# MCU.net
KiCad netlist of a schematic drawn in Altium Designer
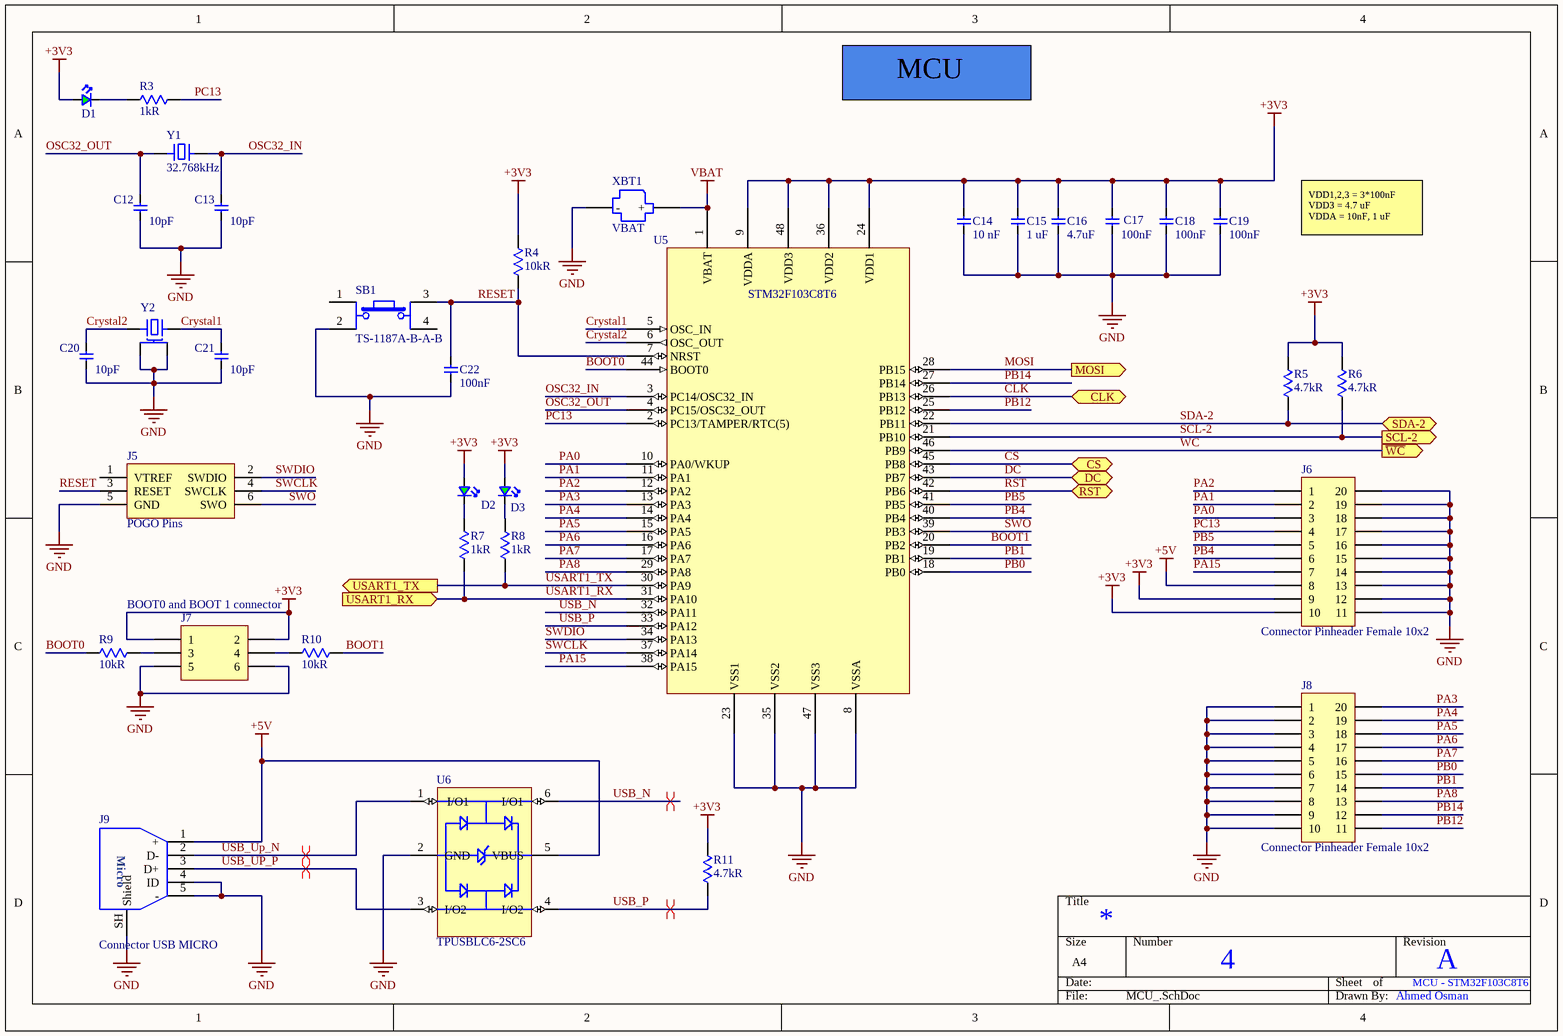
[diagram p0: MCU_.SchDoc]

(export (version "E")
  (design (tool "Eeschema 10.0.6"))
  (components
    (comp (ref "C12")
      (value "10pF")
      (footprint "CAP 0603")
      (description "10 pF ±5% 50V Ceramic Capacitor C0G, NP0 0603 (1608 Metric)")
      (fields (field (name "TOLERANCE") "5%") (field (name "VOLTAGE") "50V"))
      (libsource (lib "Temperature project symbols") (part "CAP  0603 10 pF ±5% 50V"))
    )
    (comp (ref "C13")
      (value "10pF")
      (footprint "CAP 0603")
      (description "10 pF ±5% 50V Ceramic Capacitor C0G, NP0 0603 (1608 Metric)")
      (fields (field (name "TOLERANCE") "5%") (field (name "VOLTAGE") "50V"))
      (libsource (lib "Temperature project symbols") (part "CAP  0603 10 pF ±5% 50V"))
    )
    (comp (ref "C14")
      (value "10 nF")
      (footprint "CAP 0603")
      (description "10000 pF ±10% 25V Ceramic Capacitor X7R 0603 (1608 Metric)")
      (libsource (lib "Temperature project symbols") (part "CAP  0603 10 nF ±10% 25V"))
    )
    (comp (ref "C15")
      (value "1 uF")
      (footprint "CAP 0603")
      (description "1 µF ±10% 25V Ceramic Capacitor X5R 0603 (1608 Metric)")
      (fields (field (name "MANUFACTURER") "Yageo") (field (name "TOLERANCE") "10%"))
      (libsource (lib "Temperature project symbols") (part "CAP  0603 1 µF ±10% 25V"))
    )
    (comp (ref "C16")
      (value "4.7uF")
      (footprint "CAP 0603")
      (description "4.7 µF ±10% 35V Ceramic Capacitor X5R 0603 (1608 Metric)")
      (fields (field (name "TOLERANCE") "10%") (field (name "VOLTAGE") "35V"))
      (libsource (lib "Temperature project symbols") (part "CAP  0603 4.7 µF ±10% 35V"))
    )
    (comp (ref "C17")
      (value "100nF")
      (footprint "CAP 0603")
      (description "0.1 µF ±10% 50V Ceramic Capacitor X7R 0603 (1608 Metric)")
      (fields (field (name "TOLERANCE") "10%") (field (name "VOLTAGE") "50V"))
      (libsource (lib "Temperature project symbols") (part "CAP  0603 100nF 10% 50 V"))
    )
    (comp (ref "C18")
      (value "100nF")
      (footprint "CAP 0603")
      (description "0.1 µF ±10% 50V Ceramic Capacitor X7R 0603 (1608 Metric)")
      (fields (field (name "TOLERANCE") "10%") (field (name "VOLTAGE") "50V"))
      (libsource (lib "Temperature project symbols") (part "CAP  0603 100nF 10% 50 V"))
    )
    (comp (ref "C19")
      (value "100nF")
      (footprint "CAP 0603")
      (description "0.1 µF ±10% 50V Ceramic Capacitor X7R 0603 (1608 Metric)")
      (fields (field (name "TOLERANCE") "10%") (field (name "VOLTAGE") "50V"))
      (libsource (lib "") (part "CAP  0603 100nF 10% 50 V_1"))
    )
    (comp (ref "C20")
      (value "10pF")
      (footprint "CAP 0603")
      (description "10 pF ±5% 50V Ceramic Capacitor C0G, NP0 0603 (1608 Metric)")
      (fields (field (name "TOLERANCE") "5%") (field (name "VOLTAGE") "50V"))
      (libsource (lib "Temperature project symbols") (part "CAP  0603 10 pF ±5% 50V"))
    )
    (comp (ref "C21")
      (value "10pF")
      (footprint "CAP 0603")
      (description "10 pF ±5% 50V Ceramic Capacitor C0G, NP0 0603 (1608 Metric)")
      (fields (field (name "TOLERANCE") "5%") (field (name "VOLTAGE") "50V"))
      (libsource (lib "Temperature project symbols") (part "CAP  0603 10 pF ±5% 50V"))
    )
    (comp (ref "C22")
      (value "100nF")
      (footprint "CAP 0603")
      (description "0.1 µF ±10% 50V Ceramic Capacitor X7R 0603 (1608 Metric)")
      (fields (field (name "TOLERANCE") "10%") (field (name "VOLTAGE") "50V"))
      (libsource (lib "Temperature project symbols") (part "CAP  0603 100 nF 10% 50 V"))
    )
    (comp (ref "D1")
      (value "LED GREEN")
      (footprint "LED GREEN")
      (description "Green 520nm LED Indication - Discrete 3.2V 0603 (1608 Metric)")
      (libsource (lib "Temperature project symbols") (part "LED GREEN"))
    )
    (comp (ref "D2")
      (value "LED GREEN")
      (footprint "LED GREEN")
      (description "Green 520nm LED Indication - Discrete 3.2V 0603 (1608 Metric)")
      (libsource (lib "Temperature project symbols") (part "LED GREEN"))
    )
    (comp (ref "D3")
      (value "LED GREEN")
      (footprint "LED GREEN")
      (description "Green 520nm LED Indication - Discrete 3.2V 0603 (1608 Metric)")
      (libsource (lib "Temperature project symbols") (part "LED GREEN"))
    )
    (comp (ref "J5")
      (value "POGO Pins")
      (footprint "SEGGER_8.06.16_J-LINK_6-PIN_NEEDLE_ADAPTER")
      (description "Plug-Of-Nails™ Cable Assembly")
      (libsource (lib "Temperature project symbols") (part "POGO Pins"))
    )
    (comp (ref "J6")
      (value "Connector Pinheader Female 10x2")
      (footprint "Connector Pinheader 10x2")
      (description "20 Position Header Connector 0.100\" (2.54mm) Through Hole Gold")
      (fields (field (name "MANUFACTURER") "Sullins"))
      (libsource (lib "Temperature project symbols") (part "Connector Pinheader Female 10x2"))
    )
    (comp (ref "J7")
      (value "BOOT0 and BOOT 1 connector")
      (footprint "2X3 Female Pin Header Connector")
      (libsource (lib "Temperature project symbols") (part "BOOT0 and BOOT 1 connector"))
    )
    (comp (ref "J8")
      (value "Connector Pinheader Female 10x2")
      (footprint "Connector Pinheader 10x2")
      (description "20 Position Header Connector 0.100\" (2.54mm) Through Hole Gold")
      (fields (field (name "MANUFACTURER") "Sullins"))
      (libsource (lib "Temperature project symbols") (part "Connector Pinheader Female 10x2"))
    )
    (comp (ref "J9")
      (value "Connector USB MICRO")
      (footprint "Connector USB MICRO")
      (description "1.8A USB 2.0 1 Horizontal attachment 5P Mother -20℃~+85℃ Micro-B SMD USB Connectors ROHS")
      (libsource (lib "Temperature project symbols") (part "Connector USB MICRO"))
    )
    (comp (ref "R3")
      (value "1kR")
      (footprint "RES 0603")
      (description "1 kOhms ±1% 0.1W, 1/10W Chip Resistor 0603 (1608 Metric) Moisture Resistant Thick Film")
      (fields (field (name "MANUFACTURER") "Yageo") (field (name "TOLERANCE") "1%"))
      (libsource (lib "Temperature project symbols") (part "RES  0603 1kR ±1% 0.1W"))
    )
    (comp (ref "R4")
      (value "10kR")
      (footprint "RES 0603")
      (description "10 kOhms ±1% 0.1W, 1/10W Chip Resistor 0603 (1608 Metric) Moisture Resistant Thick Film")
      (fields (field (name "TOLERANCE") "1%"))
      (libsource (lib "") (part "RES  0603 10KR ±1% 0.1W, 1/10W_1"))
    )
    (comp (ref "R5")
      (value "4.7kR")
      (footprint "RES 0603")
      (description "4.7 kOhms ±1% 0.1W, 1/10W Chip Resistor 0603 (1608 Metric) Moisture Resistant Thick Film")
      (fields (field (name "TOLERANCE") "1%"))
      (libsource (lib "Temperature project symbols") (part "RES  0603 4.7 kOhms ±1% 0.1W, 1/10W"))
    )
    (comp (ref "R6")
      (value "4.7kR")
      (footprint "RES 0603")
      (description "4.7 kOhms ±1% 0.1W, 1/10W Chip Resistor 0603 (1608 Metric) Moisture Resistant Thick Film")
      (fields (field (name "TOLERANCE") "1%"))
      (libsource (lib "Temperature project symbols") (part "RES  0603 4.7 kOhms ±1% 0.1W, 1/10W"))
    )
    (comp (ref "R7")
      (value "1kR")
      (footprint "RES 0603")
      (description "1 kOhms ±1% 0.1W, 1/10W Chip Resistor 0603 (1608 Metric) Moisture Resistant Thick Film")
      (fields (field (name "MANUFACTURER") "Yageo") (field (name "TOLERANCE") "1%"))
      (libsource (lib "Temperature project symbols") (part "RES  0603 1kR ±1% 0.1W"))
    )
    (comp (ref "R8")
      (value "1kR")
      (footprint "RES 0603")
      (description "1 kOhms ±1% 0.1W, 1/10W Chip Resistor 0603 (1608 Metric) Moisture Resistant Thick Film")
      (fields (field (name "MANUFACTURER") "Yageo") (field (name "TOLERANCE") "1%"))
      (libsource (lib "") (part "RES  0603 1kR ±1% 0.1W_1"))
    )
    (comp (ref "R9")
      (value "10kR")
      (footprint "RES 0603")
      (description "10 kOhms ±1% 0.1W, 1/10W Chip Resistor 0603 (1608 Metric) Moisture Resistant Thick Film")
      (fields (field (name "TOLERANCE") "1%"))
      (libsource (lib "Temperature project symbols") (part "RES  0603 10KR ±1% 0.1W, 1/10W"))
    )
    (comp (ref "R10")
      (value "10kR")
      (footprint "RES 0603")
      (description "10 kOhms ±1% 0.1W, 1/10W Chip Resistor 0603 (1608 Metric) Moisture Resistant Thick Film")
      (fields (field (name "TOLERANCE") "1%"))
      (libsource (lib "Temperature project symbols") (part "RES  0603 10KR ±1% 0.1W, 1/10W"))
    )
    (comp (ref "R11")
      (value "4.7kR")
      (footprint "RES 0603")
      (description "4.7 kOhms ±1% 0.1W, 1/10W Chip Resistor 0603 (1608 Metric) Moisture Resistant Thick Film")
      (fields (field (name "TOLERANCE") "1%"))
      (libsource (lib "Temperature project symbols") (part "RES  0603 4.7 kOhms ±1% 0.1W, 1/10W"))
    )
    (comp (ref "SB1")
      (value "TS-1187A-B-A-B")
      (footprint "Switch")
      (libsource (lib "Temperature project symbols") (part "TS-1187A-B-A-B"))
    )
    (comp (ref "U5")
      (value "STM32F103C8T6")
      (footprint "STM32F103C8T6")
      (description "ARM® Cortex®-M3 STM32F1 Microcontroller IC 32-Bit Single-Core 72MHz 64KB (64K x 8) FLASH")
      (libsource (lib "Temperature project symbols") (part "STM32F103C8T6"))
    )
    (comp (ref "U6")
      (value "TPUSBLC6-2SC6")
      (footprint "SOT-23-6")
      (description "SOT-23-6 ESD and Surge Protection (TVS/ESD) ROHS")
      (libsource (lib "Temperature project symbols") (part "TPUSBLC6-2SC6"))
    )
    (comp (ref "XBT1")
      (value "VBAT")
      (footprint "Battery Holder VBAT")
      (description "Battery holder CR2032 SMD Button And Strip Battery Connector ROHS")
      (libsource (lib "Temperature project symbols") (part "VBAT"))
    )
    (comp (ref "Y1")
      (value "32.768kHz")
      (footprint "SMD2012-2P")
      (description "32.768kHz Surface Mount Crystal 7pF ±20ppm SMD2012-2P Crystals ROHS")
      (libsource (lib "Temperature project symbols") (part "Crystal 32.768kHz"))
    )
    (comp (ref "Y2")
      (value "Crystal 10pF ±10ppm ±15ppm SMD3225")
      (footprint "SMD3225-4P")
      (description "8MHz Surface Mount Crystal 10pF ±10ppm ±15ppm SMD3225-4P Crystals ROHS")
      (libsource (lib "Temperature project symbols") (part "Crystal 10pF ±10ppm ±15ppm SMD3225"))
    )
  )
  (nets
    (net (code "1") (name "+3V3") (class "Default")
      (node (ref "C14") (pin "2") (pintype "passive"))
      (node (ref "C15") (pin "2") (pintype "passive"))
      (node (ref "C16") (pin "2") (pintype "passive"))
      (node (ref "C17") (pin "2") (pintype "passive"))
      (node (ref "C18") (pin "2") (pintype "passive"))
      (node (ref "C19") (pin "2") (pintype "passive"))
      (node (ref "D1") (pin "2") (pinfunction "2_2") (pintype "passive"))
      (node (ref "D2") (pin "2") (pinfunction "2_2") (pintype "passive"))
      (node (ref "D3") (pin "2") (pinfunction "2_2") (pintype "passive"))
      (node (ref "J6") (pin "10") (pinfunction "10_10") (pintype "passive"))
      (node (ref "J6") (pin "9") (pinfunction "9_9") (pintype "passive"))
      (node (ref "J7") (pin "1") (pinfunction "1_1") (pintype "passive"))
      (node (ref "J7") (pin "2") (pinfunction "2_2") (pintype "passive"))
      (node (ref "R11") (pin "2") (pinfunction "2_2") (pintype "passive"))
      (node (ref "R4") (pin "2") (pinfunction "2_2") (pintype "passive"))
      (node (ref "R5") (pin "2") (pinfunction "2_2") (pintype "passive"))
      (node (ref "R6") (pin "2") (pinfunction "2_2") (pintype "passive"))
      (node (ref "U5") (pin "24") (pinfunction "VDD1_24") (pintype "power_in"))
      (node (ref "U5") (pin "36") (pinfunction "VDD2_36") (pintype "power_in"))
      (node (ref "U5") (pin "48") (pinfunction "VDD3_48") (pintype "power_in"))
      (node (ref "U5") (pin "9") (pinfunction "VDDA_9") (pintype "power_in"))
    )
    (net (code "2") (name "+5V") (class "Default")
      (node (ref "J6") (pin "8") (pinfunction "8_8") (pintype "passive"))
      (node (ref "J9") (pin "1") (pinfunction "+_1") (pintype "passive"))
      (node (ref "U6") (pin "5") (pinfunction "VBUS_5") (pintype "passive"))
    )
    (net (code "3") (name "/BOOT0") (class "Default")
      (node (ref "R9") (pin "1") (pinfunction "1_1") (pintype "passive"))
      (node (ref "U5") (pin "44") (pinfunction "BOOT0_44") (pintype "input"))
    )
    (net (code "4") (name "/BOOT1") (class "Default")
      (node (ref "R10") (pin "2") (pinfunction "2_2") (pintype "passive"))
      (node (ref "U5") (pin "20") (pinfunction "PB2_20") (pintype "bidirectional"))
    )
    (net (code "5") (name "/CLK") (class "Default")
      (node (ref "U5") (pin "26") (pinfunction "PB13_26") (pintype "bidirectional"))
    )
    (net (code "6") (name "/CS") (class "Default")
      (node (ref "U5") (pin "45") (pinfunction "PB8_45") (pintype "bidirectional"))
    )
    (net (code "7") (name "/Crystal1") (class "Default")
      (node (ref "C21") (pin "2") (pintype "passive"))
      (node (ref "U5") (pin "5") (pinfunction "OSC_IN_5") (pintype "input"))
      (node (ref "Y2") (pin "3") (pinfunction "3_3") (pintype "passive"))
    )
    (net (code "8") (name "/Crystal2") (class "Default")
      (node (ref "C20") (pin "2") (pintype "passive"))
      (node (ref "U5") (pin "6") (pinfunction "OSC_OUT_6") (pintype "output"))
      (node (ref "Y2") (pin "1") (pinfunction "1_1") (pintype "passive"))
    )
    (net (code "9") (name "/DC") (class "Default")
      (node (ref "U5") (pin "43") (pinfunction "PB7_43") (pintype "bidirectional"))
    )
    (net (code "10") (name "/MOSI") (class "Default")
      (node (ref "U5") (pin "28") (pinfunction "PB15_28") (pintype "bidirectional"))
    )
    (net (code "11") (name "/OSC32_IN") (class "Default")
      (node (ref "C13") (pin "2") (pintype "passive"))
      (node (ref "U5") (pin "3") (pinfunction "PC14/OSC32_IN_3") (pintype "bidirectional"))
      (node (ref "Y1") (pin "2") (pinfunction "2_2") (pintype "passive"))
    )
    (net (code "12") (name "/OSC32_OUT") (class "Default")
      (node (ref "C12") (pin "2") (pintype "passive"))
      (node (ref "U5") (pin "4") (pinfunction "PC15/OSC32_OUT_4") (pintype "bidirectional"))
      (node (ref "Y1") (pin "1") (pinfunction "1_1") (pintype "passive"))
    )
    (net (code "13") (name "/PA0") (class "Default")
      (node (ref "J6") (pin "3") (pinfunction "3_3") (pintype "passive"))
      (node (ref "U5") (pin "10") (pinfunction "PA0/WKUP_10") (pintype "bidirectional"))
    )
    (net (code "14") (name "/PA1") (class "Default")
      (node (ref "J6") (pin "2") (pinfunction "2_2") (pintype "passive"))
      (node (ref "U5") (pin "11") (pinfunction "PA1_11") (pintype "bidirectional"))
    )
    (net (code "15") (name "/PA2") (class "Default")
      (node (ref "J6") (pin "1") (pinfunction "1_1") (pintype "passive"))
      (node (ref "U5") (pin "12") (pinfunction "PA2_12") (pintype "bidirectional"))
    )
    (net (code "16") (name "/PA3") (class "Default")
      (node (ref "J8") (pin "20") (pinfunction "20_20") (pintype "passive"))
      (node (ref "U5") (pin "13") (pinfunction "PA3_13") (pintype "bidirectional"))
    )
    (net (code "17") (name "/PA4") (class "Default")
      (node (ref "J8") (pin "19") (pinfunction "19_19") (pintype "passive"))
      (node (ref "U5") (pin "14") (pinfunction "PA4_14") (pintype "bidirectional"))
    )
    (net (code "18") (name "/PA5") (class "Default")
      (node (ref "J8") (pin "18") (pinfunction "18_18") (pintype "passive"))
      (node (ref "U5") (pin "15") (pinfunction "PA5_15") (pintype "bidirectional"))
    )
    (net (code "19") (name "/PA6") (class "Default")
      (node (ref "J8") (pin "17") (pinfunction "17_17") (pintype "passive"))
      (node (ref "U5") (pin "16") (pinfunction "PA6_16") (pintype "bidirectional"))
    )
    (net (code "20") (name "/PA7") (class "Default")
      (node (ref "J8") (pin "16") (pinfunction "16_16") (pintype "passive"))
      (node (ref "U5") (pin "17") (pinfunction "PA7_17") (pintype "bidirectional"))
    )
    (net (code "21") (name "/PA8") (class "Default")
      (node (ref "J8") (pin "13") (pinfunction "13_13") (pintype "passive"))
      (node (ref "U5") (pin "29") (pinfunction "PA8_29") (pintype "bidirectional"))
    )
    (net (code "22") (name "/PA15") (class "Default")
      (node (ref "J6") (pin "7") (pinfunction "7_7") (pintype "passive"))
      (node (ref "U5") (pin "38") (pinfunction "PA15_38") (pintype "bidirectional"))
    )
    (net (code "23") (name "/PB0") (class "Default")
      (node (ref "J8") (pin "15") (pinfunction "15_15") (pintype "passive"))
      (node (ref "U5") (pin "18") (pinfunction "PB0_18") (pintype "bidirectional"))
    )
    (net (code "24") (name "/PB1") (class "Default")
      (node (ref "J8") (pin "14") (pinfunction "14_14") (pintype "passive"))
      (node (ref "U5") (pin "19") (pinfunction "PB1_19") (pintype "bidirectional"))
    )
    (net (code "25") (name "/PB4") (class "Default")
      (node (ref "J6") (pin "6") (pinfunction "6_6") (pintype "passive"))
      (node (ref "U5") (pin "40") (pinfunction "PB4_40") (pintype "bidirectional"))
    )
    (net (code "26") (name "/PB5") (class "Default")
      (node (ref "J6") (pin "5") (pinfunction "5_5") (pintype "passive"))
      (node (ref "U5") (pin "41") (pinfunction "PB5_41") (pintype "bidirectional"))
    )
    (net (code "27") (name "/PB12") (class "Default")
      (node (ref "J8") (pin "11") (pinfunction "11_11") (pintype "passive"))
      (node (ref "U5") (pin "25") (pinfunction "PB12_25") (pintype "bidirectional"))
    )
    (net (code "28") (name "/PB14") (class "Default")
      (node (ref "J8") (pin "12") (pinfunction "12_12") (pintype "passive"))
      (node (ref "U5") (pin "27") (pinfunction "PB14_27") (pintype "bidirectional"))
    )
    (net (code "29") (name "/PC13") (class "Default")
      (node (ref "J6") (pin "4") (pinfunction "4_4") (pintype "passive"))
      (node (ref "R3") (pin "2") (pinfunction "2_2") (pintype "passive"))
      (node (ref "U5") (pin "2") (pinfunction "PC13/TAMPER/RTC(5)_2") (pintype "bidirectional"))
    )
    (net (code "30") (name "/RESET") (class "Default")
      (node (ref "C22") (pin "2") (pintype "passive"))
      (node (ref "J5") (pin "3") (pinfunction "RESET_3") (pintype "passive"))
      (node (ref "R4") (pin "1") (pinfunction "1_1") (pintype "passive"))
      (node (ref "SB1") (pin "3") (pinfunction "3_3") (pintype "passive"))
      (node (ref "U5") (pin "7") (pinfunction "NRST_7") (pintype "bidirectional"))
    )
    (net (code "31") (name "/RST") (class "Default")
      (node (ref "U5") (pin "42") (pinfunction "PB6_42") (pintype "bidirectional"))
    )
    (net (code "32") (name "/SCL-2") (class "Default")
      (node (ref "R6") (pin "1") (pinfunction "1_1") (pintype "passive"))
      (node (ref "U5") (pin "21") (pinfunction "PB10_21") (pintype "bidirectional"))
    )
    (net (code "33") (name "/SDA-2") (class "Default")
      (node (ref "R5") (pin "1") (pinfunction "1_1") (pintype "passive"))
      (node (ref "U5") (pin "22") (pinfunction "PB11_22") (pintype "bidirectional"))
    )
    (net (code "34") (name "/SWCLK") (class "Default")
      (node (ref "J5") (pin "4") (pinfunction "SWCLK_4") (pintype "passive"))
      (node (ref "U5") (pin "37") (pinfunction "PA14_37") (pintype "bidirectional"))
    )
    (net (code "35") (name "/SWDIO") (class "Default")
      (node (ref "J5") (pin "2") (pinfunction "SWDIO_2") (pintype "passive"))
      (node (ref "U5") (pin "34") (pinfunction "PA13_34") (pintype "bidirectional"))
    )
    (net (code "36") (name "/SWO") (class "Default")
      (node (ref "J5") (pin "6") (pinfunction "SWO_6") (pintype "passive"))
      (node (ref "U5") (pin "39") (pinfunction "PB3_39") (pintype "bidirectional"))
    )
    (net (code "37") (name "/USART1_RX") (class "Default")
      (node (ref "R7") (pin "1") (pinfunction "1_1") (pintype "passive"))
      (node (ref "U5") (pin "31") (pinfunction "PA10_31") (pintype "bidirectional"))
    )
    (net (code "38") (name "/USART1_TX") (class "Default")
      (node (ref "R8") (pin "1") (pinfunction "1_1") (pintype "passive"))
      (node (ref "U5") (pin "30") (pinfunction "PA9_30") (pintype "bidirectional"))
    )
    (net (code "39") (name "/USB_N") (class "Default")
      (node (ref "U5") (pin "32") (pinfunction "PA11_32") (pintype "bidirectional"))
      (node (ref "U6") (pin "6") (pinfunction "I/O1_6") (pintype "bidirectional"))
    )
    (net (code "40") (name "/USB_P") (class "Default")
      (node (ref "R11") (pin "1") (pinfunction "1_1") (pintype "passive"))
      (node (ref "U5") (pin "33") (pinfunction "PA12_33") (pintype "bidirectional"))
      (node (ref "U6") (pin "4") (pinfunction "I/O2_4") (pintype "bidirectional"))
    )
    (net (code "41") (name "/USB_UP_P") (class "Default")
      (node (ref "J9") (pin "3") (pinfunction "D+_3") (pintype "passive"))
      (node (ref "U6") (pin "3") (pinfunction "I/O2_3") (pintype "bidirectional"))
    )
    (net (code "42") (name "/USB_Up_N") (class "Default")
      (node (ref "J9") (pin "2") (pinfunction "D-_2") (pintype "passive"))
      (node (ref "U6") (pin "1") (pinfunction "I/O1_1") (pintype "bidirectional"))
    )
    (net (code "43") (name "/~{WC}") (class "Default")
      (node (ref "U5") (pin "46") (pinfunction "PB9_46") (pintype "bidirectional"))
    )
    (net (code "44") (name "GND") (class "Default")
      (node (ref "C12") (pin "1") (pintype "passive"))
      (node (ref "C13") (pin "1") (pintype "passive"))
      (node (ref "C14") (pin "1") (pintype "passive"))
      (node (ref "C15") (pin "1") (pintype "passive"))
      (node (ref "C16") (pin "1") (pintype "passive"))
      (node (ref "C17") (pin "1") (pintype "passive"))
      (node (ref "C18") (pin "1") (pintype "passive"))
      (node (ref "C19") (pin "1") (pintype "passive"))
      (node (ref "C20") (pin "1") (pintype "passive"))
      (node (ref "C21") (pin "1") (pintype "passive"))
      (node (ref "C22") (pin "1") (pintype "passive"))
      (node (ref "J5") (pin "5") (pinfunction "GND_5") (pintype "passive"))
      (node (ref "J6") (pin "11") (pinfunction "11_11") (pintype "passive"))
      (node (ref "J6") (pin "12") (pinfunction "12_12") (pintype "passive"))
      (node (ref "J6") (pin "13") (pinfunction "13_13") (pintype "passive"))
      (node (ref "J6") (pin "14") (pinfunction "14_14") (pintype "passive"))
      (node (ref "J6") (pin "15") (pinfunction "15_15") (pintype "passive"))
      (node (ref "J6") (pin "16") (pinfunction "16_16") (pintype "passive"))
      (node (ref "J6") (pin "17") (pinfunction "17_17") (pintype "passive"))
      (node (ref "J6") (pin "18") (pinfunction "18_18") (pintype "passive"))
      (node (ref "J6") (pin "19") (pinfunction "19_19") (pintype "passive"))
      (node (ref "J6") (pin "20") (pinfunction "20_20") (pintype "passive"))
      (node (ref "J7") (pin "5") (pinfunction "5_5") (pintype "passive"))
      (node (ref "J7") (pin "6") (pinfunction "6_6") (pintype "passive"))
      (node (ref "J8") (pin "1") (pinfunction "1_1") (pintype "passive"))
      (node (ref "J8") (pin "10") (pinfunction "10_10") (pintype "passive"))
      (node (ref "J8") (pin "2") (pinfunction "2_2") (pintype "passive"))
      (node (ref "J8") (pin "3") (pinfunction "3_3") (pintype "passive"))
      (node (ref "J8") (pin "4") (pinfunction "4_4") (pintype "passive"))
      (node (ref "J8") (pin "5") (pinfunction "5_5") (pintype "passive"))
      (node (ref "J8") (pin "6") (pinfunction "6_6") (pintype "passive"))
      (node (ref "J8") (pin "7") (pinfunction "7_7") (pintype "passive"))
      (node (ref "J8") (pin "8") (pinfunction "8_8") (pintype "passive"))
      (node (ref "J8") (pin "9") (pinfunction "9_9") (pintype "passive"))
      (node (ref "J9") (pin "4") (pinfunction "ID_4") (pintype "passive"))
      (node (ref "J9") (pin "5") (pinfunction "-_5") (pintype "passive"))
      (node (ref "J9") (pin "SH") (pinfunction "Shield_SH") (pintype "passive"))
      (node (ref "SB1") (pin "2") (pinfunction "2_2") (pintype "passive"))
      (node (ref "U5") (pin "23") (pinfunction "VSS1_23") (pintype "power_in"))
      (node (ref "U5") (pin "35") (pinfunction "VSS2_35") (pintype "power_in"))
      (node (ref "U5") (pin "47") (pinfunction "VSS3_47") (pintype "power_in"))
      (node (ref "U5") (pin "8") (pinfunction "VSSA_8") (pintype "power_in"))
      (node (ref "U6") (pin "2") (pinfunction "GND_2") (pintype "passive"))
      (node (ref "XBT1") (pin "1") (pinfunction "-_1") (pintype "passive"))
      (node (ref "Y2") (pin "2") (pinfunction "GND_2") (pintype "passive"))
      (node (ref "Y2") (pin "4") (pinfunction "GND_4") (pintype "passive"))
    )
    (net (code "45") (name "Net-(D1-Pad1)") (class "Default")
      (node (ref "D1") (pin "1") (pinfunction "1_1") (pintype "passive"))
      (node (ref "R3") (pin "1") (pinfunction "1_1") (pintype "passive"))
    )
    (net (code "46") (name "Net-(D2-Pad1)") (class "Default")
      (node (ref "D2") (pin "1") (pinfunction "1_1") (pintype "passive"))
      (node (ref "R7") (pin "2") (pinfunction "2_2") (pintype "passive"))
    )
    (net (code "47") (name "Net-(D3-Pad1)") (class "Default")
      (node (ref "D3") (pin "1") (pinfunction "1_1") (pintype "passive"))
      (node (ref "R8") (pin "2") (pinfunction "2_2") (pintype "passive"))
    )
    (net (code "48") (name "Net-(J7-Pad3)") (class "Default")
      (node (ref "J7") (pin "3") (pinfunction "3_3") (pintype "passive"))
      (node (ref "R9") (pin "2") (pinfunction "2_2") (pintype "passive"))
    )
    (net (code "49") (name "Net-(J7-Pad4)") (class "Default")
      (node (ref "J7") (pin "4") (pinfunction "4_4") (pintype "passive"))
      (node (ref "R10") (pin "1") (pinfunction "1_1") (pintype "passive"))
    )
    (net (code "50") (name "VBAT") (class "Default")
      (node (ref "U5") (pin "1") (pinfunction "VBAT_1") (pintype "power_in"))
      (node (ref "XBT1") (pin "2") (pinfunction "+_2") (pintype "passive"))
    )
    (net (code "51") (name "unconnected-(J5-VTREF-Pad1)") (class "Default")
      (node (ref "J5") (pin "1") (pinfunction "VTREF_1") (pintype "passive"))
    )
    (net (code "52") (name "unconnected-(SB1-Pad1)") (class "Default")
      (node (ref "SB1") (pin "1") (pinfunction "1_1") (pintype "passive"))
    )
    (net (code "53") (name "unconnected-(SB1-Pad4)") (class "Default")
      (node (ref "SB1") (pin "4") (pinfunction "4_4") (pintype "passive"))
    )
  )
)
